# PCB_route_Linda_KartikaSari_13215015.net
KiCad netlist of a schematic drawn in EAGLE
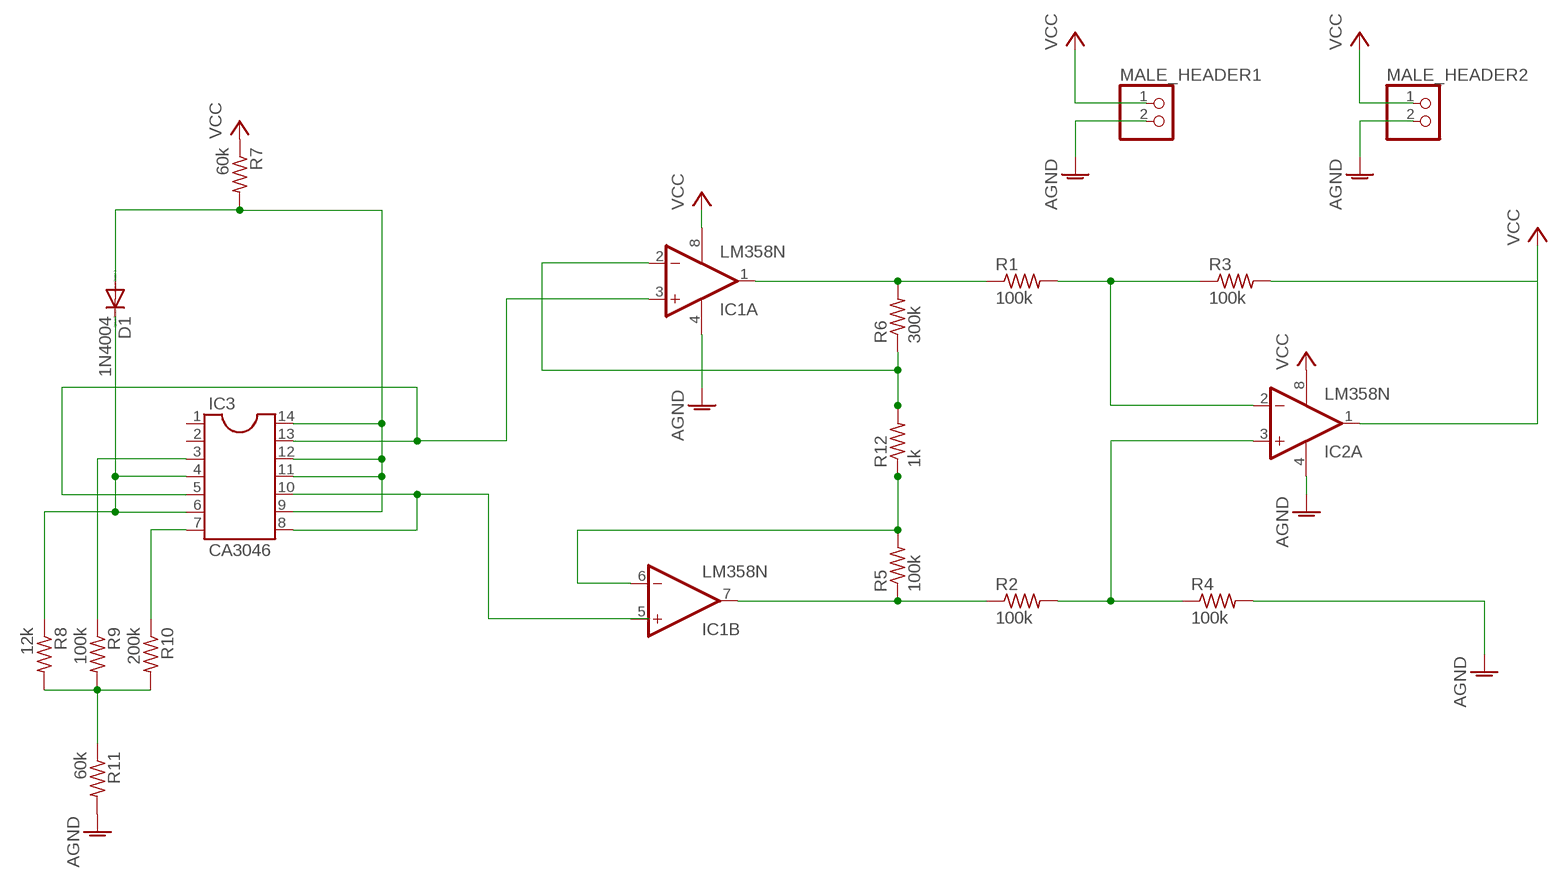
[diagram p0: schematic, sheet 1]

(export (version "E")
  (design (tool "Eeschema 10.0.6"))
  (components
    (comp (ref "D1")
      (value "1N4004")
      (footprint "eagle-import:D-7.5")
      (libsource (lib "eagle-import") (part "DIODE-D-7.5"))
    )
    (comp (ref "IC1")
      (value "LM358N")
      (footprint "eagle-import:DIL08")
      (libsource (lib "eagle-import") (part "LM358N"))
    )
    (comp (ref "IC2")
      (value "LM358N")
      (footprint "eagle-import:DIL08")
      (libsource (lib "eagle-import") (part "LM358N"))
    )
    (comp (ref "IC3")
      (value "CA3046")
      (footprint "eagle-import:DIL14")
      (libsource (lib "eagle-import") (part "DIL14"))
    )
    (comp (ref "MALE_HEADER1")
      (value "PINHD-1X2")
      (footprint "eagle-import:1X02")
      (libsource (lib "eagle-import") (part "PINHD-1X2"))
    )
    (comp (ref "MALE_HEADER2")
      (value "PINHD-1X2")
      (footprint "eagle-import:1X02")
      (libsource (lib "eagle-import") (part "PINHD-1X2"))
    )
    (comp (ref "R1")
      (value "100k")
      (footprint "eagle-import:0204_7")
      (libsource (lib "eagle-import") (part "R-US_0204/7"))
    )
    (comp (ref "R2")
      (value "100k")
      (footprint "eagle-import:0204_7")
      (libsource (lib "eagle-import") (part "R-US_0204/7"))
    )
    (comp (ref "R3")
      (value "100k")
      (footprint "eagle-import:0204_7")
      (libsource (lib "eagle-import") (part "R-US_0204/7"))
    )
    (comp (ref "R4")
      (value "100k")
      (footprint "eagle-import:0204_7")
      (libsource (lib "eagle-import") (part "R-US_0204/7"))
    )
    (comp (ref "R5")
      (value "100k")
      (footprint "eagle-import:0204_7")
      (libsource (lib "eagle-import") (part "R-US_0204/7"))
    )
    (comp (ref "R6")
      (value "300k")
      (footprint "eagle-import:0204_7")
      (libsource (lib "eagle-import") (part "R-US_0204/7"))
    )
    (comp (ref "R7")
      (value "60k")
      (footprint "eagle-import:0204_7")
      (libsource (lib "eagle-import") (part "R-US_0204/7"))
    )
    (comp (ref "R8")
      (value "12k")
      (footprint "eagle-import:0204_7")
      (libsource (lib "eagle-import") (part "R-US_0204/7"))
    )
    (comp (ref "R9")
      (value "100k")
      (footprint "eagle-import:0204_7")
      (libsource (lib "eagle-import") (part "R-US_0204/7"))
    )
    (comp (ref "R10")
      (value "200k")
      (footprint "eagle-import:0204_7")
      (libsource (lib "eagle-import") (part "R-US_0204/7"))
    )
    (comp (ref "R11")
      (value "60k")
      (footprint "eagle-import:0204_7")
      (libsource (lib "eagle-import") (part "R-US_0204/7"))
    )
    (comp (ref "R12")
      (value "1k")
      (footprint "eagle-import:0204_7")
      (libsource (lib "eagle-import") (part "R-US_0204/7"))
    )
  )
  (nets
    (net (code "1") (name "AGND") (class "Default")
      (node (ref "IC1") (pin "4") (pinfunction "V-_4") (pintype "power_in"))
      (node (ref "IC2") (pin "4") (pinfunction "V-_4") (pintype "power_in"))
      (node (ref "MALE_HEADER1") (pin "2") (pinfunction "2_2") (pintype "passive"))
      (node (ref "MALE_HEADER2") (pin "2") (pinfunction "2_2") (pintype "passive"))
      (node (ref "R11") (pin "2") (pinfunction "2_2") (pintype "passive"))
      (node (ref "R4") (pin "2") (pinfunction "2_2") (pintype "passive"))
    )
    (net (code "2") (name "Net-(D1-PadC)") (class "Default")
      (node (ref "D1") (pin "C") (pinfunction "C_C") (pintype "passive"))
      (node (ref "IC3") (pin "4") (pinfunction "4_4") (pintype "passive"))
      (node (ref "IC3") (pin "6") (pinfunction "6_6") (pintype "passive"))
      (node (ref "R8") (pin "1") (pinfunction "1_1") (pintype "passive"))
    )
    (net (code "3") (name "Net-(IC1A-+IN)") (class "Default")
      (node (ref "D1") (pin "A") (pinfunction "A_A") (pintype "passive"))
      (node (ref "IC1") (pin "3") (pinfunction "+IN_3") (pintype "input"))
      (node (ref "IC3") (pin "11") (pinfunction "11_11") (pintype "passive"))
      (node (ref "IC3") (pin "12") (pinfunction "12_12") (pintype "passive"))
      (node (ref "IC3") (pin "13") (pinfunction "13_13") (pintype "passive"))
      (node (ref "IC3") (pin "14") (pinfunction "14_14") (pintype "passive"))
      (node (ref "IC3") (pin "5") (pinfunction "5_5") (pintype "passive"))
      (node (ref "IC3") (pin "9") (pinfunction "9_9") (pintype "passive"))
      (node (ref "R7") (pin "2") (pinfunction "2_2") (pintype "passive"))
    )
    (net (code "4") (name "Net-(IC1A--IN)") (class "Default")
      (node (ref "IC1") (pin "2") (pinfunction "-IN_2") (pintype "input"))
      (node (ref "R12") (pin "2") (pinfunction "2_2") (pintype "passive"))
      (node (ref "R6") (pin "1") (pinfunction "1_1") (pintype "passive"))
    )
    (net (code "5") (name "Net-(IC1A-OUT)") (class "Default")
      (node (ref "IC1") (pin "1") (pinfunction "OUT_1") (pintype "output"))
      (node (ref "R1") (pin "1") (pinfunction "1_1") (pintype "passive"))
      (node (ref "R6") (pin "2") (pinfunction "2_2") (pintype "passive"))
    )
    (net (code "6") (name "Net-(IC1B-+IN)") (class "Default")
      (node (ref "IC1") (pin "5") (pinfunction "+IN_5") (pintype "input"))
      (node (ref "IC3") (pin "10") (pinfunction "10_10") (pintype "passive"))
      (node (ref "IC3") (pin "8") (pinfunction "8_8") (pintype "passive"))
    )
    (net (code "7") (name "Net-(IC1B--IN)") (class "Default")
      (node (ref "IC1") (pin "6") (pinfunction "-IN_6") (pintype "input"))
      (node (ref "R12") (pin "1") (pinfunction "1_1") (pintype "passive"))
      (node (ref "R5") (pin "2") (pinfunction "2_2") (pintype "passive"))
    )
    (net (code "8") (name "Net-(IC1B-OUT)") (class "Default")
      (node (ref "IC1") (pin "7") (pinfunction "OUT_7") (pintype "output"))
      (node (ref "R2") (pin "1") (pinfunction "1_1") (pintype "passive"))
      (node (ref "R5") (pin "1") (pinfunction "1_1") (pintype "passive"))
    )
    (net (code "9") (name "Net-(IC2A-+IN)") (class "Default")
      (node (ref "IC2") (pin "3") (pinfunction "+IN_3") (pintype "input"))
      (node (ref "R2") (pin "2") (pinfunction "2_2") (pintype "passive"))
      (node (ref "R4") (pin "1") (pinfunction "1_1") (pintype "passive"))
    )
    (net (code "10") (name "Net-(IC2A--IN)") (class "Default")
      (node (ref "IC2") (pin "2") (pinfunction "-IN_2") (pintype "input"))
      (node (ref "R1") (pin "2") (pinfunction "2_2") (pintype "passive"))
      (node (ref "R3") (pin "1") (pinfunction "1_1") (pintype "passive"))
    )
    (net (code "11") (name "Net-(IC3-Pad3)") (class "Default")
      (node (ref "IC3") (pin "3") (pinfunction "3_3") (pintype "passive"))
      (node (ref "R9") (pin "1") (pinfunction "1_1") (pintype "passive"))
    )
    (net (code "12") (name "Net-(IC3-Pad7)") (class "Default")
      (node (ref "IC3") (pin "7") (pinfunction "7_7") (pintype "passive"))
      (node (ref "R10") (pin "1") (pinfunction "1_1") (pintype "passive"))
    )
    (net (code "13") (name "Net-(R10-Pad2)") (class "Default")
      (node (ref "R10") (pin "2") (pinfunction "2_2") (pintype "passive"))
      (node (ref "R11") (pin "1") (pinfunction "1_1") (pintype "passive"))
      (node (ref "R8") (pin "2") (pinfunction "2_2") (pintype "passive"))
      (node (ref "R9") (pin "2") (pinfunction "2_2") (pintype "passive"))
    )
    (net (code "14") (name "VCC") (class "Default")
      (node (ref "IC1") (pin "8") (pinfunction "V+_8") (pintype "power_in"))
      (node (ref "IC2") (pin "1") (pinfunction "OUT_1") (pintype "output"))
      (node (ref "IC2") (pin "8") (pinfunction "V+_8") (pintype "power_in"))
      (node (ref "MALE_HEADER1") (pin "1") (pinfunction "1_1") (pintype "passive"))
      (node (ref "MALE_HEADER2") (pin "1") (pinfunction "1_1") (pintype "passive"))
      (node (ref "R3") (pin "2") (pinfunction "2_2") (pintype "passive"))
      (node (ref "R7") (pin "1") (pinfunction "1_1") (pintype "passive"))
    )
    (net (code "15") (name "unconnected-(IC3-Pad1)") (class "Default")
      (node (ref "IC3") (pin "1") (pinfunction "1_1") (pintype "passive"))
    )
    (net (code "16") (name "unconnected-(IC3-Pad2)") (class "Default")
      (node (ref "IC3") (pin "2") (pinfunction "2_2") (pintype "passive"))
    )
  )
)
